# interface.net
KiCad netlist of a schematic drawn in EAGLE
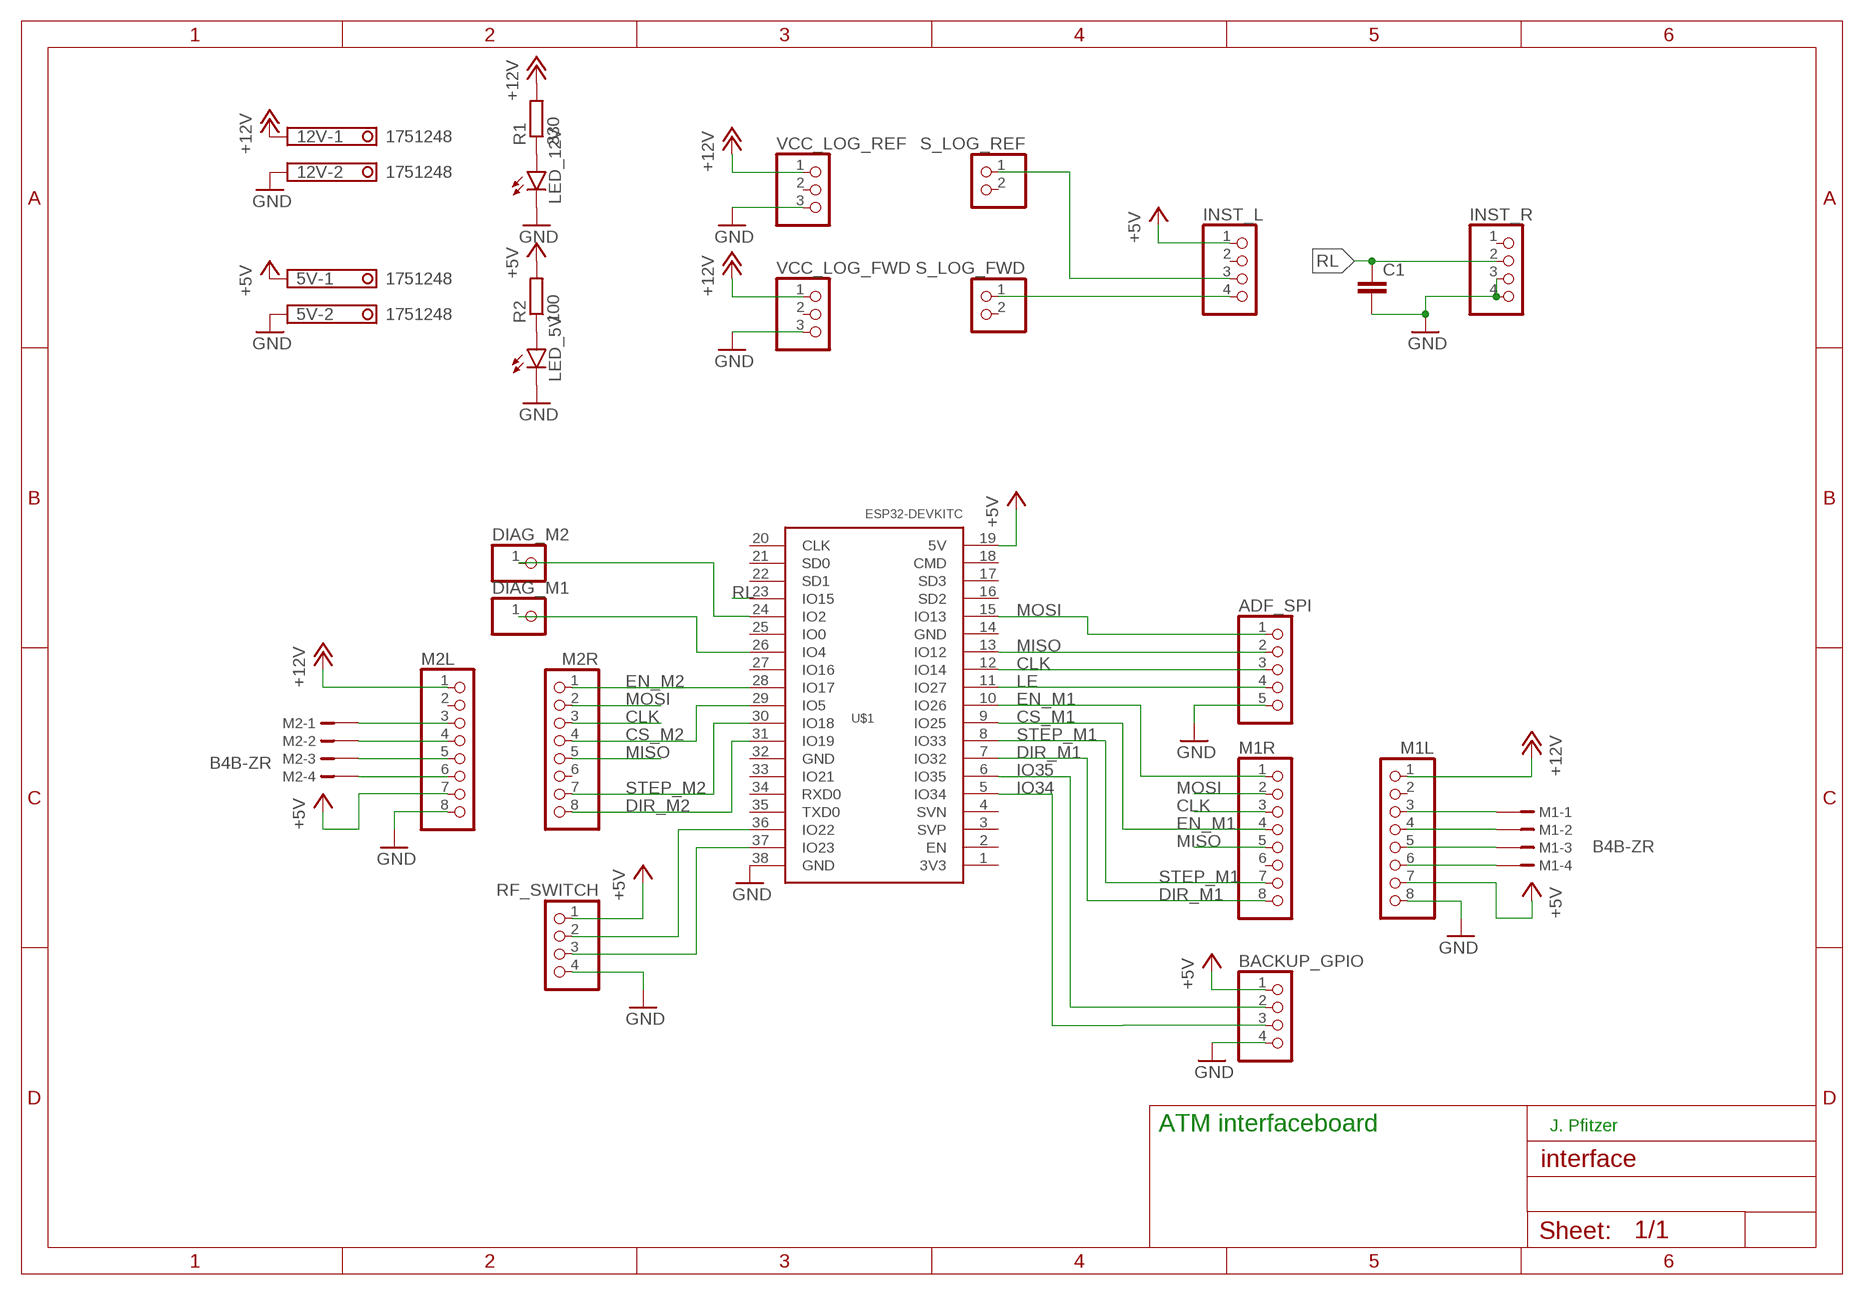
[diagram p0: schematic, sheet 1]

(export (version "E")
  (design (tool "Eeschema 10.0.6"))
  (components
    (comp (ref "5V")
      (value "1751248")
      (footprint "eagle-import:1751248")
      (libsource (lib "eagle-import") (part "1751248"))
    )
    (comp (ref "12V")
      (value "1751248")
      (footprint "eagle-import:1751248")
      (libsource (lib "eagle-import") (part "1751248"))
    )
    (comp (ref "ADF_SPI")
      (value "PINHD-1X5")
      (footprint "eagle-import:1X05")
      (libsource (lib "eagle-import") (part "PINHD-1X5"))
    )
    (comp (ref "BACKUP_GPIO")
      (value "PINHD-1X4")
      (footprint "eagle-import:1X04")
      (libsource (lib "eagle-import") (part "PINHD-1X4"))
    )
    (comp (ref "C1")
      (value "C-EU025-025X050")
      (footprint "eagle-import:C025-025X050")
      (libsource (lib "eagle-import") (part "C-EU025-025X050"))
    )
    (comp (ref "DIAG_M1")
      (value "PINHD-1X1")
      (footprint "eagle-import:1X01")
      (libsource (lib "eagle-import") (part "PINHD-1X1"))
    )
    (comp (ref "DIAG_M2")
      (value "PINHD-1X1")
      (footprint "eagle-import:1X01")
      (libsource (lib "eagle-import") (part "PINHD-1X1"))
    )
    (comp (ref "INST_L")
      (value "PINHD-1X4")
      (footprint "eagle-import:1X04")
      (libsource (lib "eagle-import") (part "PINHD-1X4"))
    )
    (comp (ref "INST_R")
      (value "PINHD-1X4")
      (footprint "eagle-import:1X04")
      (libsource (lib "eagle-import") (part "PINHD-1X4"))
    )
    (comp (ref "LED_5V")
      (value "LED5MM")
      (footprint "eagle-import:LED5MM")
      (libsource (lib "eagle-import") (part "LED5MM"))
    )
    (comp (ref "LED_12V")
      (value "LED5MM")
      (footprint "eagle-import:LED5MM")
      (libsource (lib "eagle-import") (part "LED5MM"))
    )
    (comp (ref "M1")
      (value "B4B-ZR")
      (footprint "eagle-import:B4B-ZR")
      (fields (field (name "MF") "FARNELL") (field (name "MPN") "B4B-ZR(LF)(SN)"))
      (libsource (lib "eagle-import") (part "?4B-ZRB"))
    )
    (comp (ref "M1L")
      (value "PINHD-1X8")
      (footprint "eagle-import:1X08")
      (libsource (lib "eagle-import") (part "PINHD-1X8"))
    )
    (comp (ref "M1R")
      (value "PINHD-1X8")
      (footprint "eagle-import:1X08")
      (libsource (lib "eagle-import") (part "PINHD-1X8"))
    )
    (comp (ref "M2")
      (value "B4B-ZR")
      (footprint "eagle-import:B4B-ZR")
      (fields (field (name "MF") "FARNELL") (field (name "MPN") "B4B-ZR(LF)(SN)"))
      (libsource (lib "eagle-import") (part "?4B-ZRB"))
    )
    (comp (ref "M2L")
      (value "PINHD-1X8")
      (footprint "eagle-import:1X08")
      (libsource (lib "eagle-import") (part "PINHD-1X8"))
    )
    (comp (ref "M2R")
      (value "PINHD-1X8")
      (footprint "eagle-import:1X08")
      (libsource (lib "eagle-import") (part "PINHD-1X8"))
    )
    (comp (ref "R1")
      (value "330")
      (footprint "eagle-import:0207_12")
      (libsource (lib "eagle-import") (part "R-EU_0207/12"))
    )
    (comp (ref "R2")
      (value "100")
      (footprint "eagle-import:0207_12")
      (libsource (lib "eagle-import") (part "R-EU_0207/12"))
    )
    (comp (ref "RF_SWITCH")
      (value "PINHD-1X4")
      (footprint "eagle-import:1X04")
      (libsource (lib "eagle-import") (part "PINHD-1X4"))
    )
    (comp (ref "S_LOG_FWD")
      (value "PINHD-1X2")
      (footprint "eagle-import:1X02")
      (libsource (lib "eagle-import") (part "PINHD-1X2"))
    )
    (comp (ref "S_LOG_REF")
      (value "PINHD-1X2")
      (footprint "eagle-import:1X02")
      (libsource (lib "eagle-import") (part "PINHD-1X2"))
    )
    (comp (ref "U$1")
      (value "ESP32DEVKITC")
      (footprint "eagle-import:ESP32-DEVKITC")
      (libsource (lib "eagle-import") (part "ESP32DEVKITC"))
    )
    (comp (ref "VCC_LOG_FWD")
      (value "PINHD-1X3")
      (footprint "eagle-import:1X03")
      (libsource (lib "eagle-import") (part "PINHD-1X3"))
    )
    (comp (ref "VCC_LOG_REF")
      (value "PINHD-1X3")
      (footprint "eagle-import:1X03")
      (libsource (lib "eagle-import") (part "PINHD-1X3"))
    )
  )
  (nets
    (net (code "1") (name "+5V") (class "Default")
      (node (ref "5V") (pin "1") (pinfunction "K_1") (pintype "passive"))
      (node (ref "BACKUP_GPIO") (pin "1") (pinfunction "1_1") (pintype "passive"))
      (node (ref "INST_L") (pin "1") (pinfunction "1_1") (pintype "passive"))
      (node (ref "M1L") (pin "7") (pinfunction "7_7") (pintype "passive"))
      (node (ref "M2L") (pin "7") (pinfunction "7_7") (pintype "passive"))
      (node (ref "R2") (pin "2") (pinfunction "2_2") (pintype "passive"))
      (node (ref "RF_SWITCH") (pin "1") (pinfunction "1_1") (pintype "passive"))
      (node (ref "U$1") (pin "19") (pinfunction "5V_19") (pintype "bidirectional"))
    )
    (net (code "2") (name "+12V") (class "Default")
      (node (ref "12V") (pin "1") (pinfunction "K_1") (pintype "passive"))
      (node (ref "M1L") (pin "1") (pinfunction "1_1") (pintype "passive"))
      (node (ref "M2L") (pin "1") (pinfunction "1_1") (pintype "passive"))
      (node (ref "R1") (pin "2") (pinfunction "2_2") (pintype "passive"))
      (node (ref "VCC_LOG_FWD") (pin "1") (pinfunction "1_1") (pintype "passive"))
      (node (ref "VCC_LOG_REF") (pin "1") (pinfunction "1_1") (pintype "passive"))
    )
    (net (code "3") (name "/CLK") (class "Default")
      (node (ref "ADF_SPI") (pin "3") (pinfunction "3_3") (pintype "passive"))
      (node (ref "M1R") (pin "3") (pinfunction "3_3") (pintype "passive"))
      (node (ref "M2R") (pin "3") (pinfunction "3_3") (pintype "passive"))
      (node (ref "U$1") (pin "12") (pinfunction "IO14_12") (pintype "bidirectional"))
    )
    (net (code "4") (name "/CS_M1") (class "Default")
      (node (ref "M1R") (pin "4") (pinfunction "4_4") (pintype "passive"))
      (node (ref "U$1") (pin "9") (pinfunction "IO25_9") (pintype "bidirectional"))
    )
    (net (code "5") (name "/CS_M2") (class "Default")
      (node (ref "M2R") (pin "4") (pinfunction "4_4") (pintype "passive"))
      (node (ref "U$1") (pin "29") (pinfunction "IO5_29") (pintype "bidirectional"))
    )
    (net (code "6") (name "/DIR_M1") (class "Default")
      (node (ref "M1R") (pin "8") (pinfunction "8_8") (pintype "passive"))
      (node (ref "U$1") (pin "7") (pinfunction "IO32_7") (pintype "bidirectional"))
    )
    (net (code "7") (name "/DIR_M2") (class "Default")
      (node (ref "M2R") (pin "8") (pinfunction "8_8") (pintype "passive"))
      (node (ref "U$1") (pin "31") (pinfunction "IO19_31") (pintype "bidirectional"))
    )
    (net (code "8") (name "/EN_M1") (class "Default")
      (node (ref "M1R") (pin "1") (pinfunction "1_1") (pintype "passive"))
      (node (ref "U$1") (pin "10") (pinfunction "IO26_10") (pintype "bidirectional"))
    )
    (net (code "9") (name "/EN_M2") (class "Default")
      (node (ref "M2R") (pin "1") (pinfunction "1_1") (pintype "passive"))
      (node (ref "U$1") (pin "28") (pinfunction "IO17_28") (pintype "bidirectional"))
    )
    (net (code "10") (name "/IO34") (class "Default")
      (node (ref "BACKUP_GPIO") (pin "3") (pinfunction "3_3") (pintype "passive"))
      (node (ref "U$1") (pin "5") (pinfunction "IO34_5") (pintype "bidirectional"))
    )
    (net (code "11") (name "/IO35") (class "Default")
      (node (ref "BACKUP_GPIO") (pin "2") (pinfunction "2_2") (pintype "passive"))
      (node (ref "U$1") (pin "6") (pinfunction "IO35_6") (pintype "bidirectional"))
    )
    (net (code "12") (name "/LE") (class "Default")
      (node (ref "ADF_SPI") (pin "4") (pinfunction "4_4") (pintype "passive"))
      (node (ref "U$1") (pin "11") (pinfunction "IO27_11") (pintype "bidirectional"))
    )
    (net (code "13") (name "/MISO") (class "Default")
      (node (ref "ADF_SPI") (pin "2") (pinfunction "2_2") (pintype "passive"))
      (node (ref "M1R") (pin "5") (pinfunction "5_5") (pintype "passive"))
      (node (ref "M2R") (pin "5") (pinfunction "5_5") (pintype "passive"))
      (node (ref "U$1") (pin "13") (pinfunction "IO12_13") (pintype "bidirectional"))
    )
    (net (code "14") (name "/MOSI") (class "Default")
      (node (ref "ADF_SPI") (pin "1") (pinfunction "1_1") (pintype "passive"))
      (node (ref "M1R") (pin "2") (pinfunction "2_2") (pintype "passive"))
      (node (ref "M2R") (pin "2") (pinfunction "2_2") (pintype "passive"))
      (node (ref "U$1") (pin "15") (pinfunction "IO13_15") (pintype "bidirectional"))
    )
    (net (code "15") (name "/STEP_M1") (class "Default")
      (node (ref "M1R") (pin "7") (pinfunction "7_7") (pintype "passive"))
      (node (ref "U$1") (pin "8") (pinfunction "IO33_8") (pintype "bidirectional"))
    )
    (net (code "16") (name "/STEP_M2") (class "Default")
      (node (ref "M2R") (pin "7") (pinfunction "7_7") (pintype "passive"))
      (node (ref "U$1") (pin "30") (pinfunction "IO18_30") (pintype "bidirectional"))
    )
    (net (code "17") (name "GND") (class "Default")
      (node (ref "12V") (pin "2") (pinfunction "K_2") (pintype "passive"))
      (node (ref "5V") (pin "2") (pinfunction "K_2") (pintype "passive"))
      (node (ref "ADF_SPI") (pin "5") (pinfunction "5_5") (pintype "passive"))
      (node (ref "BACKUP_GPIO") (pin "4") (pinfunction "4_4") (pintype "passive"))
      (node (ref "C1") (pin "2") (pinfunction "2_2") (pintype "passive"))
      (node (ref "INST_R") (pin "3") (pinfunction "3_3") (pintype "passive"))
      (node (ref "INST_R") (pin "4") (pinfunction "4_4") (pintype "passive"))
      (node (ref "LED_12V") (pin "K") (pinfunction "C_K") (pintype "passive"))
      (node (ref "LED_5V") (pin "K") (pinfunction "C_K") (pintype "passive"))
      (node (ref "M1L") (pin "8") (pinfunction "8_8") (pintype "passive"))
      (node (ref "M2L") (pin "8") (pinfunction "8_8") (pintype "passive"))
      (node (ref "RF_SWITCH") (pin "4") (pinfunction "4_4") (pintype "passive"))
      (node (ref "U$1") (pin "38") (pinfunction "GND_38") (pintype "bidirectional"))
      (node (ref "VCC_LOG_FWD") (pin "3") (pinfunction "3_3") (pintype "passive"))
      (node (ref "VCC_LOG_REF") (pin "3") (pinfunction "3_3") (pintype "passive"))
    )
    (net (code "18") (name "Net-(INST_L-Pad3)") (class "Default")
      (node (ref "INST_L") (pin "3") (pinfunction "3_3") (pintype "passive"))
      (node (ref "S_LOG_REF") (pin "1") (pinfunction "1_1") (pintype "passive"))
    )
    (net (code "19") (name "Net-(INST_L-Pad4)") (class "Default")
      (node (ref "INST_L") (pin "4") (pinfunction "4_4") (pintype "passive"))
      (node (ref "S_LOG_FWD") (pin "1") (pinfunction "1_1") (pintype "passive"))
    )
    (net (code "20") (name "Net-(LED_5V-PadA)") (class "Default")
      (node (ref "LED_5V") (pin "A") (pinfunction "A_A") (pintype "passive"))
      (node (ref "R2") (pin "1") (pinfunction "1_1") (pintype "passive"))
    )
    (net (code "21") (name "Net-(LED_12V-PadA)") (class "Default")
      (node (ref "LED_12V") (pin "A") (pinfunction "A_A") (pintype "passive"))
      (node (ref "R1") (pin "1") (pinfunction "1_1") (pintype "passive"))
    )
    (net (code "22") (name "Net-(M1-Pad1)") (class "Default")
      (node (ref "M1") (pin "1") (pinfunction "1_1") (pintype "passive"))
      (node (ref "M1L") (pin "3") (pinfunction "3_3") (pintype "passive"))
    )
    (net (code "23") (name "Net-(M1B-1)") (class "Default")
      (node (ref "M1") (pin "2") (pinfunction "1_2") (pintype "passive"))
      (node (ref "M1L") (pin "4") (pinfunction "4_4") (pintype "passive"))
    )
    (net (code "24") (name "Net-(M1C-1)") (class "Default")
      (node (ref "M1") (pin "3") (pinfunction "1_3") (pintype "passive"))
      (node (ref "M1L") (pin "5") (pinfunction "5_5") (pintype "passive"))
    )
    (net (code "25") (name "Net-(M1D-1)") (class "Default")
      (node (ref "M1") (pin "4") (pinfunction "1_4") (pintype "passive"))
      (node (ref "M1L") (pin "6") (pinfunction "6_6") (pintype "passive"))
    )
    (net (code "26") (name "Net-(M2-Pad1)") (class "Default")
      (node (ref "M2") (pin "1") (pinfunction "1_1") (pintype "passive"))
      (node (ref "M2L") (pin "3") (pinfunction "3_3") (pintype "passive"))
    )
    (net (code "27") (name "Net-(M2B-1)") (class "Default")
      (node (ref "M2") (pin "2") (pinfunction "1_2") (pintype "passive"))
      (node (ref "M2L") (pin "4") (pinfunction "4_4") (pintype "passive"))
    )
    (net (code "28") (name "Net-(M2C-1)") (class "Default")
      (node (ref "M2") (pin "3") (pinfunction "1_3") (pintype "passive"))
      (node (ref "M2L") (pin "5") (pinfunction "5_5") (pintype "passive"))
    )
    (net (code "29") (name "Net-(M2D-1)") (class "Default")
      (node (ref "M2") (pin "4") (pinfunction "1_4") (pintype "passive"))
      (node (ref "M2L") (pin "6") (pinfunction "6_6") (pintype "passive"))
    )
    (net (code "30") (name "Net-(U$1-IO2)") (class "Default")
      (node (ref "DIAG_M2") (pin "1") (pinfunction "1_1") (pintype "passive"))
      (node (ref "U$1") (pin "24") (pinfunction "IO2_24") (pintype "bidirectional"))
    )
    (net (code "31") (name "Net-(U$1-IO4)") (class "Default")
      (node (ref "DIAG_M1") (pin "1") (pinfunction "1_1") (pintype "passive"))
      (node (ref "U$1") (pin "26") (pinfunction "IO4_26") (pintype "bidirectional"))
    )
    (net (code "32") (name "Net-(U$1-IO22)") (class "Default")
      (node (ref "RF_SWITCH") (pin "2") (pinfunction "2_2") (pintype "passive"))
      (node (ref "U$1") (pin "36") (pinfunction "IO22_36") (pintype "bidirectional"))
    )
    (net (code "33") (name "Net-(U$1-IO23)") (class "Default")
      (node (ref "RF_SWITCH") (pin "3") (pinfunction "3_3") (pintype "passive"))
      (node (ref "U$1") (pin "37") (pinfunction "IO23_37") (pintype "bidirectional"))
    )
    (net (code "34") (name "RL") (class "Default")
      (node (ref "C1") (pin "1") (pinfunction "1_1") (pintype "passive"))
      (node (ref "INST_R") (pin "2") (pinfunction "2_2") (pintype "passive"))
      (node (ref "U$1") (pin "23") (pinfunction "IO15_23") (pintype "bidirectional"))
    )
    (net (code "35") (name "unconnected-(INST_L-Pad2)") (class "Default")
      (node (ref "INST_L") (pin "2") (pinfunction "2_2") (pintype "passive"))
    )
    (net (code "36") (name "unconnected-(INST_R-Pad1)") (class "Default")
      (node (ref "INST_R") (pin "1") (pinfunction "1_1") (pintype "passive"))
    )
    (net (code "37") (name "unconnected-(M1L-Pad2)") (class "Default")
      (node (ref "M1L") (pin "2") (pinfunction "2_2") (pintype "passive"))
    )
    (net (code "38") (name "unconnected-(M1R-Pad6)") (class "Default")
      (node (ref "M1R") (pin "6") (pinfunction "6_6") (pintype "passive"))
    )
    (net (code "39") (name "unconnected-(M2L-Pad2)") (class "Default")
      (node (ref "M2L") (pin "2") (pinfunction "2_2") (pintype "passive"))
    )
    (net (code "40") (name "unconnected-(M2R-Pad6)") (class "Default")
      (node (ref "M2R") (pin "6") (pinfunction "6_6") (pintype "passive"))
    )
    (net (code "41") (name "unconnected-(S_LOG_FWD-Pad2)") (class "Default")
      (node (ref "S_LOG_FWD") (pin "2") (pinfunction "2_2") (pintype "passive"))
    )
    (net (code "42") (name "unconnected-(S_LOG_REF-Pad2)") (class "Default")
      (node (ref "S_LOG_REF") (pin "2") (pinfunction "2_2") (pintype "passive"))
    )
    (net (code "43") (name "unconnected-(U$1-3V3-Pad1)") (class "Default")
      (node (ref "U$1") (pin "1") (pinfunction "3V3_1") (pintype "bidirectional"))
    )
    (net (code "44") (name "unconnected-(U$1-CLK-Pad20)") (class "Default")
      (node (ref "U$1") (pin "20") (pinfunction "CLK_20") (pintype "bidirectional"))
    )
    (net (code "45") (name "unconnected-(U$1-CMD-Pad18)") (class "Default")
      (node (ref "U$1") (pin "18") (pinfunction "CMD_18") (pintype "bidirectional"))
    )
    (net (code "46") (name "unconnected-(U$1-EN-Pad2)") (class "Default")
      (node (ref "U$1") (pin "2") (pinfunction "EN_2") (pintype "bidirectional"))
    )
    (net (code "47") (name "unconnected-(U$1-GND-Pad14)") (class "Default")
      (node (ref "U$1") (pin "14") (pinfunction "GND_14") (pintype "bidirectional"))
    )
    (net (code "48") (name "unconnected-(U$1-GND-Pad32)") (class "Default")
      (node (ref "U$1") (pin "32") (pinfunction "GND_32") (pintype "bidirectional"))
    )
    (net (code "49") (name "unconnected-(U$1-IO0-Pad25)") (class "Default")
      (node (ref "U$1") (pin "25") (pinfunction "IO0_25") (pintype "bidirectional"))
    )
    (net (code "50") (name "unconnected-(U$1-IO16-Pad27)") (class "Default")
      (node (ref "U$1") (pin "27") (pinfunction "IO16_27") (pintype "bidirectional"))
    )
    (net (code "51") (name "unconnected-(U$1-IO21-Pad33)") (class "Default")
      (node (ref "U$1") (pin "33") (pinfunction "IO21_33") (pintype "bidirectional"))
    )
    (net (code "52") (name "unconnected-(U$1-RXD0-Pad34)") (class "Default")
      (node (ref "U$1") (pin "34") (pinfunction "RXD0_34") (pintype "bidirectional"))
    )
    (net (code "53") (name "unconnected-(U$1-SD0-Pad21)") (class "Default")
      (node (ref "U$1") (pin "21") (pinfunction "SD0_21") (pintype "bidirectional"))
    )
    (net (code "54") (name "unconnected-(U$1-SD1-Pad22)") (class "Default")
      (node (ref "U$1") (pin "22") (pinfunction "SD1_22") (pintype "bidirectional"))
    )
    (net (code "55") (name "unconnected-(U$1-SD2-Pad16)") (class "Default")
      (node (ref "U$1") (pin "16") (pinfunction "SD2_16") (pintype "bidirectional"))
    )
    (net (code "56") (name "unconnected-(U$1-SD3-Pad17)") (class "Default")
      (node (ref "U$1") (pin "17") (pinfunction "SD3_17") (pintype "bidirectional"))
    )
    (net (code "57") (name "unconnected-(U$1-SVN-Pad4)") (class "Default")
      (node (ref "U$1") (pin "4") (pinfunction "SVN_4") (pintype "bidirectional"))
    )
    (net (code "58") (name "unconnected-(U$1-SVP-Pad3)") (class "Default")
      (node (ref "U$1") (pin "3") (pinfunction "SVP_3") (pintype "bidirectional"))
    )
    (net (code "59") (name "unconnected-(U$1-TXD0-Pad35)") (class "Default")
      (node (ref "U$1") (pin "35") (pinfunction "TXD0_35") (pintype "bidirectional"))
    )
    (net (code "60") (name "unconnected-(VCC_LOG_FWD-Pad2)") (class "Default")
      (node (ref "VCC_LOG_FWD") (pin "2") (pinfunction "2_2") (pintype "passive"))
    )
    (net (code "61") (name "unconnected-(VCC_LOG_REF-Pad2)") (class "Default")
      (node (ref "VCC_LOG_REF") (pin "2") (pinfunction "2_2") (pintype "passive"))
    )
  )
)
